# knixx_HAT_00.net
KiCad netlist of a schematic drawn in Altium Designer
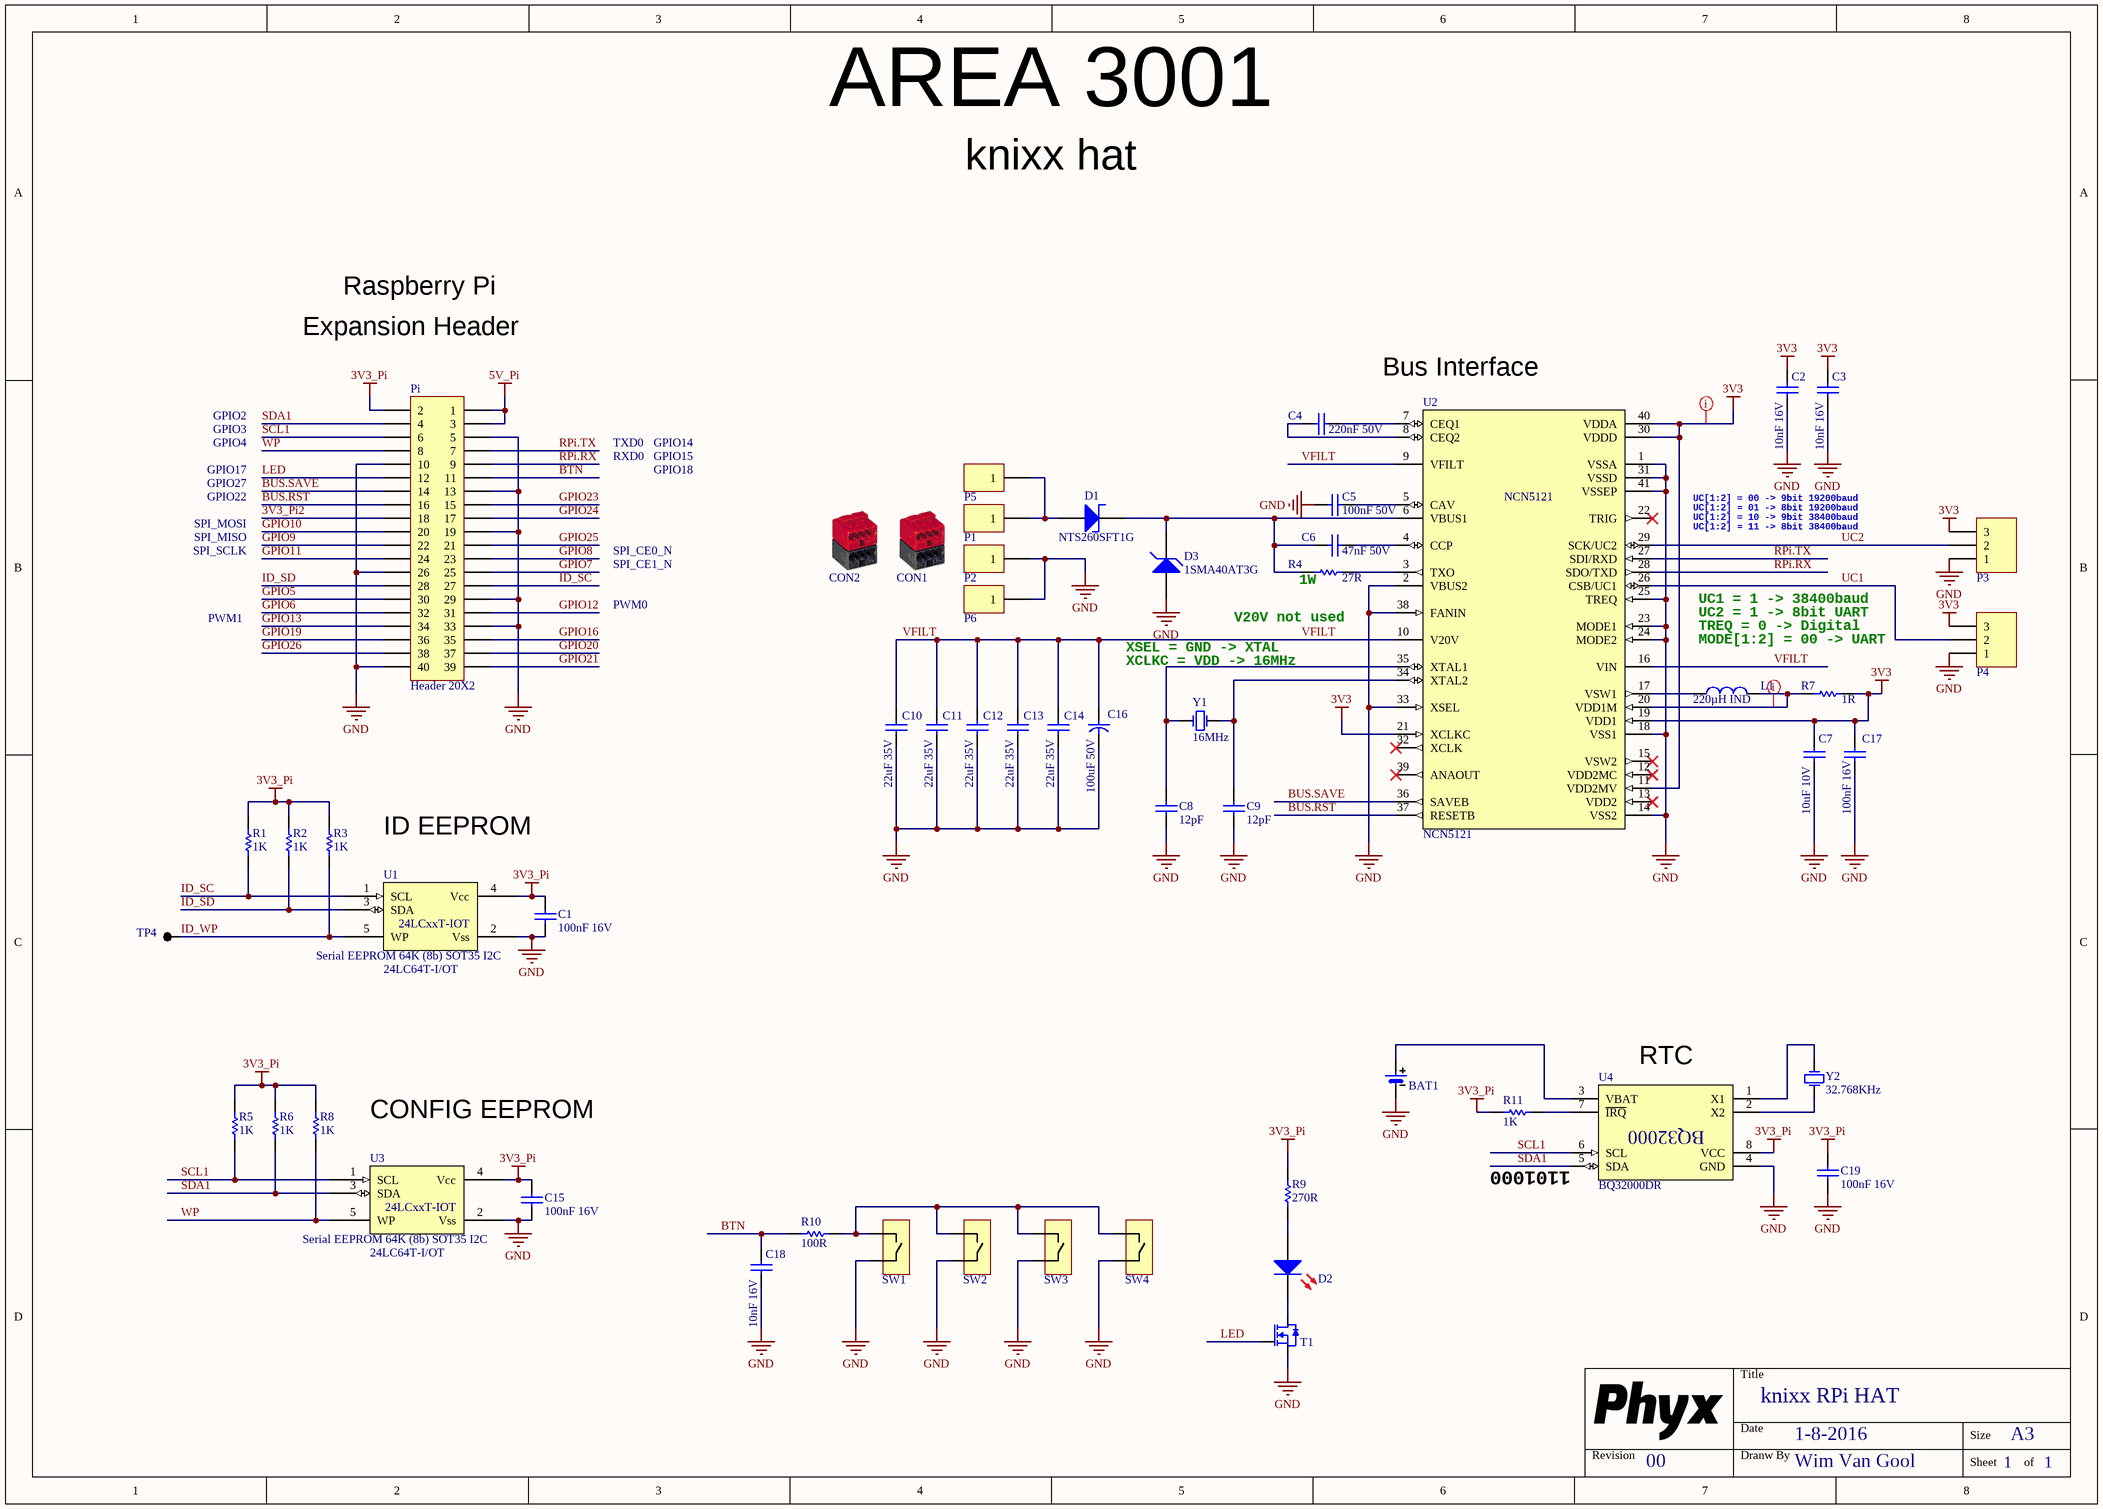
[diagram p0: knixx_HAT_00.SchDoc]

(export (version "E")
  (design (tool "Eeschema 10.0.6"))
  (components
    (comp (ref "BAT1")
      (value "BR-1220/HFN 35mAh")
      (footprint "BR-1220_HFN")
      (description "=Description")
      (libsource (lib "Phyx_Components") (part "BAT_2"))
    )
    (comp (ref "C1")
      (value "100nF 16V")
      (footprint "C0603_N")
      (description "Capacitor Ceramic")
      (fields (field (name "Comment") "CAP_CERAMIC"))
      (libsource (lib "Phyx_Components") (part "CAP_CERAMIC"))
    )
    (comp (ref "C2")
      (value "10nF 16V")
      (footprint "C0603_N")
      (description "Capacitor Ceramic")
      (fields (field (name "Comment") "CAP_CERAMIC"))
      (libsource (lib "Phyx_Components") (part "CAP_CERAMIC"))
    )
    (comp (ref "C3")
      (value "10nF 16V")
      (footprint "C0603_N")
      (description "Capacitor Ceramic")
      (fields (field (name "Comment") "CAP_CERAMIC"))
      (libsource (lib "Phyx_Components") (part "CAP_CERAMIC"))
    )
    (comp (ref "C4")
      (value "220nF 50V")
      (footprint "C0805_N")
      (description "Capacitor Ceramic")
      (fields (field (name "Comment") "CAP_CERAMIC"))
      (libsource (lib "Phyx_Components") (part "CAP_CERAMIC"))
    )
    (comp (ref "C5")
      (value "100nF 50V")
      (footprint "C0603_N")
      (description "Capacitor Ceramic")
      (fields (field (name "Comment") "CAP_CERAMIC"))
      (libsource (lib "Phyx_Components") (part "CAP_CERAMIC"))
    )
    (comp (ref "C6")
      (value "47nF 50V")
      (footprint "C0603_N")
      (description "Capacitor Ceramic")
      (fields (field (name "Comment") "CAP_CERAMIC"))
      (libsource (lib "Phyx_Components") (part "CAP_CERAMIC"))
    )
    (comp (ref "C7")
      (value "10uF 10V")
      (footprint "C0805_N")
      (description "Capacitor Ceramic")
      (fields (field (name "Comment") "CAP_CERAMIC"))
      (libsource (lib "Phyx_Components") (part "CAP_CERAMIC"))
    )
    (comp (ref "C8")
      (value "12pF")
      (footprint "C0603_N")
      (description "Capacitor Ceramic")
      (fields (field (name "Comment") "CAP_CERAMIC"))
      (libsource (lib "Phyx_Components") (part "CAP_CERAMIC"))
    )
    (comp (ref "C9")
      (value "12pF")
      (footprint "C0603_N")
      (description "Capacitor Ceramic")
      (fields (field (name "Comment") "CAP_CERAMIC"))
      (libsource (lib "Phyx_Components") (part "CAP_CERAMIC"))
    )
    (comp (ref "C10")
      (value "22uF 35V")
      (footprint "C1206_N")
      (description "Capacitor Ceramic")
      (fields (field (name "Comment") "CAP_CERAMIC"))
      (libsource (lib "Phyx_Components") (part "CAP_CERAMIC"))
    )
    (comp (ref "C11")
      (value "22uF 35V")
      (footprint "C1206_N")
      (description "Capacitor Ceramic")
      (fields (field (name "Comment") "CAP_CERAMIC"))
      (libsource (lib "Phyx_Components") (part "CAP_CERAMIC"))
    )
    (comp (ref "C12")
      (value "22uF 35V")
      (footprint "C1206_N")
      (description "Capacitor Ceramic")
      (fields (field (name "Comment") "CAP_CERAMIC"))
      (libsource (lib "Phyx_Components") (part "CAP_CERAMIC"))
    )
    (comp (ref "C13")
      (value "22uF 35V")
      (footprint "C1206_N")
      (description "Capacitor Ceramic")
      (fields (field (name "Comment") "CAP_CERAMIC"))
      (libsource (lib "Phyx_Components") (part "CAP_CERAMIC"))
    )
    (comp (ref "C14")
      (value "22uF 35V")
      (footprint "C1206_N")
      (description "Capacitor Ceramic")
      (fields (field (name "Comment") "CAP_CERAMIC"))
      (libsource (lib "Phyx_Components") (part "CAP_CERAMIC"))
    )
    (comp (ref "C15")
      (value "100nF 16V")
      (footprint "C0603_N")
      (description "Capacitor Ceramic")
      (fields (field (name "Comment") "CAP_CERAMIC"))
      (libsource (lib "Phyx_Components") (part "CAP_CERAMIC"))
    )
    (comp (ref "C16")
      (value "100uF 50V")
      (footprint "C_8x11.5_3.5mm")
      (description "Capacitor electrolyt")
      (fields (field (name "Comment") "CAP_POL"))
      (libsource (lib "Phyx_Components") (part "CAP_POL"))
    )
    (comp (ref "C17")
      (value "100nF 16V")
      (footprint "C0603_N")
      (description "Capacitor Ceramic")
      (fields (field (name "Comment") "CAP_CERAMIC"))
      (libsource (lib "Phyx_Components") (part "CAP_CERAMIC"))
    )
    (comp (ref "C18")
      (value "10nF 16V")
      (footprint "C0603_N")
      (description "Capacitor Ceramic")
      (fields (field (name "Comment") "CAP_CERAMIC"))
      (libsource (lib "Phyx_Components") (part "CAP_CERAMIC"))
    )
    (comp (ref "C19")
      (value "100nF 16V")
      (footprint "C0603_N")
      (description "Capacitor Ceramic")
      (fields (field (name "Comment") "CAP_CERAMIC"))
      (libsource (lib "Phyx_Components") (part "CAP_CERAMIC"))
    )
    (comp (ref "CON1")
      (value "CONNECTOR FOR EIB APPLICATIONS PUSH-WIRE® CONNECTION")
      (footprint "WAGO_243-211")
      (libsource (lib "Phyx_Components") (part "WAGO_243-211"))
    )
    (comp (ref "CON2")
      (value "CONNECTOR FOR EIB APPLICATIONS PUSH-WIRE® CONNECTION")
      (footprint "WAGO_243-211")
      (libsource (lib "Phyx_Components") (part "WAGO_243-211"))
    )
    (comp (ref "D1")
      (value "NTS260SFT1G")
      (footprint "ON_SOD-123FL")
      (description "=Description")
      (fields (field (name "Comment") "NTS260SFT1G  Schottky Rectifier, Single, 60 V, 2 A, SOD-123, 650 mV"))
      (libsource (lib "Phyx_Components") (part "Schottky_21"))
    )
    (comp (ref "D2")
      (value "Default 0805 Red LED")
      (footprint "LED_0805_RD")
      (description "=Description")
      (libsource (lib "Phyx_Components") (part "LED_RED"))
    )
    (comp (ref "D3")
      (value "1SMA40AT3G")
      (footprint "SMA_AC")
      (description "=Description")
      (fields (field (name "Comment") "TVS Diode 40V 400W Unidirectional DO-214AC"))
      (libsource (lib "Phyx_Components") (part "TVS_AC"))
    )
    (comp (ref "L1")
      (value "220µH IND")
      (footprint "IND_6045")
      (fields (field (name "Comment") "220µH INDUCTOR"))
      (libsource (lib "Phyx_Components") (part "INDUCTOR"))
    )
    (comp (ref "P1")
      (value "SOLDER PIN FOR PCBS UP TO 2 MM")
      (footprint "WAGO_243-131")
      (libsource (lib "Phyx_Components") (part "Header 1"))
    )
    (comp (ref "P2")
      (value "SOLDER PIN FOR PCBS UP TO 2 MM")
      (footprint "WAGO_243-131")
      (libsource (lib "Phyx_Components") (part "Header 1"))
    )
    (comp (ref "P3")
      (value "Header 3")
      (footprint "HDR1X3")
      (libsource (lib "Phyx_Components") (part "Header 3"))
    )
    (comp (ref "P4")
      (value "Header 3")
      (footprint "HDR1X3")
      (libsource (lib "Phyx_Components") (part "Header 3"))
    )
    (comp (ref "P5")
      (value "SOLDER PIN FOR PCBS UP TO 2 MM")
      (footprint "WAGO_243-131")
      (libsource (lib "Phyx_Components") (part "Header 1"))
    )
    (comp (ref "P6")
      (value "SOLDER PIN FOR PCBS UP TO 2 MM")
      (footprint "WAGO_243-131")
      (libsource (lib "Phyx_Components") (part "Header 1"))
    )
    (comp (ref "Pi")
      (value "Header 20X2")
      (footprint "RCPT2X20")
      (description "=Description")
      (libsource (lib "Phyx_Components") (part "Header 20X2"))
    )
    (comp (ref "R1")
      (value "1K")
      (footprint "R0603_N")
      (fields (field (name "Comment") "RESISTOR"))
      (libsource (lib "Phyx_Components") (part "RESISTOR"))
    )
    (comp (ref "R2")
      (value "1K")
      (footprint "R0603_N")
      (fields (field (name "Comment") "RESISTOR"))
      (libsource (lib "Phyx_Components") (part "RESISTOR"))
    )
    (comp (ref "R3")
      (value "1K")
      (footprint "R0603_N")
      (fields (field (name "Comment") "RESISTOR"))
      (libsource (lib "Phyx_Components") (part "RESISTOR"))
    )
    (comp (ref "R4")
      (value "27R")
      (footprint "R2512")
      (fields (field (name "Comment") "RESISTOR"))
      (libsource (lib "Phyx_Components") (part "RESISTOR"))
    )
    (comp (ref "R5")
      (value "1K")
      (footprint "R0603_N")
      (fields (field (name "Comment") "RESISTOR"))
      (libsource (lib "Phyx_Components") (part "RESISTOR"))
    )
    (comp (ref "R6")
      (value "1K")
      (footprint "R0603_N")
      (fields (field (name "Comment") "RESISTOR"))
      (libsource (lib "Phyx_Components") (part "RESISTOR"))
    )
    (comp (ref "R7")
      (value "1R")
      (footprint "R0603_N")
      (fields (field (name "Comment") "RESISTOR"))
      (libsource (lib "Phyx_Components") (part "RESISTOR"))
    )
    (comp (ref "R8")
      (value "1K")
      (footprint "R0603_N")
      (fields (field (name "Comment") "RESISTOR"))
      (libsource (lib "Phyx_Components") (part "RESISTOR"))
    )
    (comp (ref "R9")
      (value "270R")
      (footprint "R0603_N")
      (fields (field (name "Comment") "RESISTOR"))
      (libsource (lib "Phyx_Components") (part "RESISTOR"))
    )
    (comp (ref "R10")
      (value "100R")
      (footprint "R0603_N")
      (fields (field (name "Comment") "RESISTOR"))
      (libsource (lib "Phyx_Components") (part "RESISTOR"))
    )
    (comp (ref "R11")
      (value "1K")
      (footprint "R0603_N")
      (fields (field (name "Comment") "RESISTOR"))
      (libsource (lib "Phyx_Components") (part "RESISTOR"))
    )
    (comp (ref "SW1")
      (value "LP RA SMD tact sw W/BOSS")
      (footprint "EVQP7M01K")
      (libsource (lib "Phyx_Components") (part "SW_TACT"))
    )
    (comp (ref "SW2")
      (value "Default TH TACT")
      (footprint "TACTSW")
      (libsource (lib "Phyx_Components") (part "SW_TACT"))
    )
    (comp (ref "SW3")
      (value "LP RA SMD tact sw W/BOSS")
      (footprint "EVQP7M01K")
      (libsource (lib "Phyx_Components") (part "SW_TACT"))
    )
    (comp (ref "SW4")
      (value "Default TH TACT")
      (footprint "TACTSW")
      (libsource (lib "Phyx_Components") (part "SW_TACT"))
    )
    (comp (ref "T1")
      (value "0.2A N-Ch MOSFET Vgs 3.2")
      (footprint "SOT23-3")
      (libsource (lib "Phyx_Components") (part "N_MOSFET_GSD"))
    )
    (comp (ref "TP4")
      (value "TEST_PAD")
      (footprint "TP_1.2mm_0.6mm")
      (libsource (lib "Phyx_Components") (part "TEST_PAD"))
    )
    (comp (ref "U1")
      (value "Serial EEPROM 64K (8b) SOT35 I2C")
      (footprint "SOT23-5")
      (description "=Description")
      (fields (field (name "ALTIUM_VALUE") "24LC64T-I/OT"))
      (libsource (lib "Phyx_Components") (part "24LCxxT-IOT"))
    )
    (comp (ref "U2")
      (value "NCN5121")
      (footprint "ONS_QFN40_6x6")
      (description "=Description")
      (fields (field (name "Comment") "KNX Transceiver for Twisted Pair Networks"))
      (libsource (lib "Phyx_Components") (part "NCN5121"))
    )
    (comp (ref "U3")
      (value "Serial EEPROM 64K (8b) SOT35 I2C")
      (footprint "SOT23-5")
      (description "=Description")
      (fields (field (name "ALTIUM_VALUE") "24LC64T-I/OT"))
      (libsource (lib "Phyx_Components") (part "24LCxxT-IOT"))
    )
    (comp (ref "U4")
      (value "BQ32000DR")
      (footprint "SOIC_N_8")
      (description "=Description")
      (fields (field (name "Comment") "I2C RTC Ti BQ32000"))
      (libsource (lib "Phyx_Components") (part "BQ32000"))
    )
    (comp (ref "Y1")
      (value "16MHz")
      (footprint "HC49US_SMD")
      (description "Crystal Oscillator")
      (fields (field (name "Comment") "16MHz 20pF HC49S Fox"))
      (libsource (lib "Phyx_Components") (part "XTAL"))
    )
    (comp (ref "Y2")
      (value "32.768KHz")
      (footprint "CMR200T")
      (description "Crystal Oscillator")
      (fields (field (name "Comment") "32.768Khz CMR200 12.5pF"))
      (libsource (lib "Phyx_Components") (part "XTAL"))
    )
  )
  (nets
    (net (code "1") (name "/3V3_Pi2") (class "Default")
      (node (ref "Pi") (pin "18") (pinfunction "18_18") (pintype "passive"))
    )
    (net (code "2") (name "/BTN") (class "Default")
      (node (ref "C18") (pin "1") (pinfunction "1_1") (pintype "passive"))
      (node (ref "Pi") (pin "11") (pinfunction "11_11") (pintype "passive"))
      (node (ref "R10") (pin "2") (pinfunction "2_2") (pintype "passive"))
    )
    (net (code "3") (name "/BUS.RST") (class "Default")
      (node (ref "Pi") (pin "16") (pinfunction "16_16") (pintype "passive"))
      (node (ref "U2") (pin "37") (pinfunction "RESETB_37") (pintype "output"))
    )
    (net (code "4") (name "/BUS.SAVE") (class "Default")
      (node (ref "Pi") (pin "14") (pinfunction "14_14") (pintype "passive"))
      (node (ref "U2") (pin "36") (pinfunction "SAVEB_36") (pintype "output"))
    )
    (net (code "5") (name "/GPIO5") (class "Default")
      (node (ref "Pi") (pin "30") (pinfunction "30_30") (pintype "passive"))
    )
    (net (code "6") (name "/GPIO6") (class "Default")
      (node (ref "Pi") (pin "32") (pinfunction "32_32") (pintype "passive"))
    )
    (net (code "7") (name "/GPIO7") (class "Default")
      (node (ref "Pi") (pin "25") (pinfunction "25_25") (pintype "passive"))
    )
    (net (code "8") (name "/GPIO8") (class "Default")
      (node (ref "Pi") (pin "23") (pinfunction "23_23") (pintype "passive"))
    )
    (net (code "9") (name "/GPIO9") (class "Default")
      (node (ref "Pi") (pin "22") (pinfunction "22_22") (pintype "passive"))
    )
    (net (code "10") (name "/GPIO10") (class "Default")
      (node (ref "Pi") (pin "20") (pinfunction "20_20") (pintype "passive"))
    )
    (net (code "11") (name "/GPIO11") (class "Default")
      (node (ref "Pi") (pin "24") (pinfunction "24_24") (pintype "passive"))
    )
    (net (code "12") (name "/GPIO12") (class "Default")
      (node (ref "Pi") (pin "31") (pinfunction "31_31") (pintype "passive"))
    )
    (net (code "13") (name "/GPIO13") (class "Default")
      (node (ref "Pi") (pin "34") (pinfunction "34_34") (pintype "passive"))
    )
    (net (code "14") (name "/GPIO16") (class "Default")
      (node (ref "Pi") (pin "35") (pinfunction "35_35") (pintype "passive"))
    )
    (net (code "15") (name "/GPIO19") (class "Default")
      (node (ref "Pi") (pin "36") (pinfunction "36_36") (pintype "passive"))
    )
    (net (code "16") (name "/GPIO20") (class "Default")
      (node (ref "Pi") (pin "37") (pinfunction "37_37") (pintype "passive"))
    )
    (net (code "17") (name "/GPIO21") (class "Default")
      (node (ref "Pi") (pin "39") (pinfunction "39_39") (pintype "passive"))
    )
    (net (code "18") (name "/GPIO23") (class "Default")
      (node (ref "Pi") (pin "15") (pinfunction "15_15") (pintype "passive"))
    )
    (net (code "19") (name "/GPIO24") (class "Default")
      (node (ref "Pi") (pin "17") (pinfunction "17_17") (pintype "passive"))
    )
    (net (code "20") (name "/GPIO25") (class "Default")
      (node (ref "Pi") (pin "21") (pinfunction "21_21") (pintype "passive"))
    )
    (net (code "21") (name "/GPIO26") (class "Default")
      (node (ref "Pi") (pin "38") (pinfunction "38_38") (pintype "passive"))
    )
    (net (code "22") (name "/ID_SC") (class "Default")
      (node (ref "Pi") (pin "27") (pinfunction "27_27") (pintype "passive"))
      (node (ref "R1") (pin "2") (pinfunction "2_2") (pintype "passive"))
      (node (ref "U1") (pin "1") (pinfunction "SCL_1") (pintype "input"))
    )
    (net (code "23") (name "/ID_SD") (class "Default")
      (node (ref "Pi") (pin "28") (pinfunction "28_28") (pintype "passive"))
      (node (ref "R2") (pin "2") (pinfunction "2_2") (pintype "passive"))
      (node (ref "U1") (pin "3") (pinfunction "SDA_3") (pintype "bidirectional"))
    )
    (net (code "24") (name "/ID_WP") (class "Default")
      (node (ref "R3") (pin "2") (pinfunction "2_2") (pintype "passive"))
      (node (ref "TP4") (pin "1") (pinfunction "1_1") (pintype "passive"))
      (node (ref "U1") (pin "5") (pinfunction "WP_5") (pintype "passive"))
    )
    (net (code "25") (name "/LED") (class "Default")
      (node (ref "Pi") (pin "12") (pinfunction "12_12") (pintype "passive"))
      (node (ref "T1") (pin "1") (pinfunction "G_1") (pintype "passive"))
    )
    (net (code "26") (name "/RPi.RX") (class "Default")
      (node (ref "Pi") (pin "9") (pinfunction "9_9") (pintype "passive"))
      (node (ref "U2") (pin "28") (pinfunction "SDO/TXD_28") (pintype "output"))
    )
    (net (code "27") (name "/RPi.TX") (class "Default")
      (node (ref "Pi") (pin "7") (pinfunction "7_7") (pintype "passive"))
      (node (ref "U2") (pin "27") (pinfunction "SDI/RXD_27") (pintype "input"))
    )
    (net (code "28") (name "/SCL1") (class "Default")
      (node (ref "Pi") (pin "6") (pinfunction "6_6") (pintype "passive"))
      (node (ref "R5") (pin "2") (pinfunction "2_2") (pintype "passive"))
      (node (ref "U3") (pin "1") (pinfunction "SCL_1") (pintype "input"))
      (node (ref "U4") (pin "6") (pinfunction "SCL_6") (pintype "input"))
    )
    (net (code "29") (name "/SDA1") (class "Default")
      (node (ref "Pi") (pin "4") (pinfunction "4_4") (pintype "passive"))
      (node (ref "R6") (pin "2") (pinfunction "2_2") (pintype "passive"))
      (node (ref "U3") (pin "3") (pinfunction "SDA_3") (pintype "bidirectional"))
      (node (ref "U4") (pin "5") (pinfunction "SDA_5") (pintype "bidirectional"))
    )
    (net (code "30") (name "/UC1") (class "Default")
      (node (ref "P4") (pin "2") (pinfunction "2_2") (pintype "passive"))
      (node (ref "U2") (pin "26") (pinfunction "CSB/UC1_26") (pintype "bidirectional"))
    )
    (net (code "31") (name "/UC2") (class "Default")
      (node (ref "P3") (pin "2") (pinfunction "2_2") (pintype "passive"))
      (node (ref "U2") (pin "29") (pinfunction "SCK/UC2_29") (pintype "bidirectional"))
    )
    (net (code "32") (name "/VFILT") (class "Default")
      (node (ref "C10") (pin "1") (pinfunction "1_1") (pintype "passive"))
      (node (ref "C11") (pin "1") (pinfunction "1_1") (pintype "passive"))
      (node (ref "C12") (pin "1") (pinfunction "1_1") (pintype "passive"))
      (node (ref "C13") (pin "1") (pinfunction "1_1") (pintype "passive"))
      (node (ref "C14") (pin "1") (pinfunction "1_1") (pintype "passive"))
      (node (ref "C16") (pin "1") (pinfunction "1_1") (pintype "passive"))
      (node (ref "U2") (pin "10") (pinfunction "V20V_10") (pintype "power_in"))
      (node (ref "U2") (pin "16") (pinfunction "VIN_16") (pintype "power_in"))
      (node (ref "U2") (pin "9") (pinfunction "VFILT_9") (pintype "power_in"))
    )
    (net (code "33") (name "/WP") (class "Default")
      (node (ref "Pi") (pin "8") (pinfunction "8_8") (pintype "passive"))
      (node (ref "R8") (pin "2") (pinfunction "2_2") (pintype "passive"))
      (node (ref "U3") (pin "5") (pinfunction "WP_5") (pintype "passive"))
    )
    (net (code "34") (name "3V3") (class "Default")
      (node (ref "C17") (pin "1") (pinfunction "1_1") (pintype "passive"))
      (node (ref "C2") (pin "1") (pinfunction "1_1") (pintype "passive"))
      (node (ref "C3") (pin "1") (pinfunction "1_1") (pintype "passive"))
      (node (ref "C7") (pin "1") (pinfunction "1_1") (pintype "passive"))
      (node (ref "P3") (pin "3") (pinfunction "3_3") (pintype "passive"))
      (node (ref "P4") (pin "3") (pinfunction "3_3") (pintype "passive"))
      (node (ref "R7") (pin "1") (pinfunction "1_1") (pintype "passive"))
      (node (ref "U2") (pin "11") (pinfunction "VDD2MV_11") (pintype "input"))
      (node (ref "U2") (pin "19") (pinfunction "VDD1_19") (pintype "input"))
      (node (ref "U2") (pin "21") (pinfunction "XCLKC_21") (pintype "input"))
      (node (ref "U2") (pin "30") (pinfunction "VDDD_30") (pintype "power_in"))
      (node (ref "U2") (pin "40") (pinfunction "VDDA_40") (pintype "power_in"))
    )
    (net (code "35") (name "3V3_Pi") (class "Default")
      (node (ref "C1") (pin "1") (pinfunction "1_1") (pintype "passive"))
      (node (ref "C15") (pin "1") (pinfunction "1_1") (pintype "passive"))
      (node (ref "C19") (pin "1") (pinfunction "1_1") (pintype "passive"))
      (node (ref "Pi") (pin "2") (pinfunction "2_2") (pintype "passive"))
      (node (ref "R1") (pin "1") (pinfunction "1_1") (pintype "passive"))
      (node (ref "R11") (pin "1") (pinfunction "1_1") (pintype "passive"))
      (node (ref "R2") (pin "1") (pinfunction "1_1") (pintype "passive"))
      (node (ref "R3") (pin "1") (pinfunction "1_1") (pintype "passive"))
      (node (ref "R5") (pin "1") (pinfunction "1_1") (pintype "passive"))
      (node (ref "R6") (pin "1") (pinfunction "1_1") (pintype "passive"))
      (node (ref "R8") (pin "1") (pinfunction "1_1") (pintype "passive"))
      (node (ref "R9") (pin "1") (pinfunction "1_1") (pintype "passive"))
      (node (ref "U1") (pin "4") (pinfunction "Vcc_4") (pintype "passive"))
      (node (ref "U3") (pin "4") (pinfunction "Vcc_4") (pintype "passive"))
      (node (ref "U4") (pin "8") (pinfunction "VCC_8") (pintype "power_in"))
    )
    (net (code "36") (name "5V_Pi") (class "Default")
      (node (ref "Pi") (pin "1") (pinfunction "1_1") (pintype "passive"))
      (node (ref "Pi") (pin "3") (pinfunction "3_3") (pintype "passive"))
    )
    (net (code "37") (name "GND") (class "Default")
      (node (ref "BAT1") (pin "2") (pinfunction "2_2") (pintype "passive"))
      (node (ref "C1") (pin "2") (pinfunction "2_2") (pintype "passive"))
      (node (ref "C10") (pin "2") (pinfunction "2_2") (pintype "passive"))
      (node (ref "C11") (pin "2") (pinfunction "2_2") (pintype "passive"))
      (node (ref "C12") (pin "2") (pinfunction "2_2") (pintype "passive"))
      (node (ref "C13") (pin "2") (pinfunction "2_2") (pintype "passive"))
      (node (ref "C14") (pin "2") (pinfunction "2_2") (pintype "passive"))
      (node (ref "C15") (pin "2") (pinfunction "2_2") (pintype "passive"))
      (node (ref "C16") (pin "2") (pinfunction "2_2") (pintype "passive"))
      (node (ref "C17") (pin "2") (pinfunction "2_2") (pintype "passive"))
      (node (ref "C18") (pin "2") (pinfunction "2_2") (pintype "passive"))
      (node (ref "C19") (pin "2") (pinfunction "2_2") (pintype "passive"))
      (node (ref "C2") (pin "2") (pinfunction "2_2") (pintype "passive"))
      (node (ref "C3") (pin "2") (pinfunction "2_2") (pintype "passive"))
      (node (ref "C5") (pin "2") (pinfunction "2_2") (pintype "passive"))
      (node (ref "C7") (pin "2") (pinfunction "2_2") (pintype "passive"))
      (node (ref "C8") (pin "2") (pinfunction "2_2") (pintype "passive"))
      (node (ref "C9") (pin "2") (pinfunction "2_2") (pintype "passive"))
      (node (ref "D3") (pin "A") (pinfunction "A_A") (pintype "passive"))
      (node (ref "P2") (pin "1") (pinfunction "1_1") (pintype "passive"))
      (node (ref "P3") (pin "1") (pinfunction "1_1") (pintype "passive"))
      (node (ref "P4") (pin "1") (pinfunction "1_1") (pintype "passive"))
      (node (ref "P6") (pin "1") (pinfunction "1_1") (pintype "passive"))
      (node (ref "Pi") (pin "10") (pinfunction "10_10") (pintype "passive"))
      (node (ref "Pi") (pin "13") (pinfunction "13_13") (pintype "passive"))
      (node (ref "Pi") (pin "19") (pinfunction "19_19") (pintype "passive"))
      (node (ref "Pi") (pin "26") (pinfunction "26_26") (pintype "passive"))
      (node (ref "Pi") (pin "29") (pinfunction "29_29") (pintype "passive"))
      (node (ref "Pi") (pin "33") (pinfunction "33_33") (pintype "passive"))
      (node (ref "Pi") (pin "40") (pinfunction "40_40") (pintype "passive"))
      (node (ref "Pi") (pin "5") (pinfunction "5_5") (pintype "passive"))
      (node (ref "SW1") (pin "2") (pinfunction "2_2") (pintype "passive"))
      (node (ref "SW2") (pin "2") (pinfunction "2_2") (pintype "passive"))
      (node (ref "SW3") (pin "2") (pinfunction "2_2") (pintype "passive"))
      (node (ref "SW4") (pin "2") (pinfunction "2_2") (pintype "passive"))
      (node (ref "T1") (pin "2") (pinfunction "S_2") (pintype "passive"))
      (node (ref "U1") (pin "2") (pinfunction "Vss_2") (pintype "passive"))
      (node (ref "U2") (pin "1") (pinfunction "VSSA_1") (pintype "power_in"))
      (node (ref "U2") (pin "14") (pinfunction "VSS2_14") (pintype "power_in"))
      (node (ref "U2") (pin "18") (pinfunction "VSS1_18") (pintype "power_in"))
      (node (ref "U2") (pin "2") (pinfunction "VBUS2_2") (pintype "power_in"))
      (node (ref "U2") (pin "23") (pinfunction "MODE1_23") (pintype "input"))
      (node (ref "U2") (pin "24") (pinfunction "MODE2_24") (pintype "input"))
      (node (ref "U2") (pin "25") (pinfunction "TREQ_25") (pintype "input"))
      (node (ref "U2") (pin "31") (pinfunction "VSSD_31") (pintype "power_in"))
      (node (ref "U2") (pin "33") (pinfunction "XSEL_33") (pintype "input"))
      (node (ref "U2") (pin "38") (pinfunction "FANIN_38") (pintype "input"))
      (node (ref "U2") (pin "41") (pinfunction "VSSEP_41") (pintype "power_in"))
      (node (ref "U3") (pin "2") (pinfunction "Vss_2") (pintype "passive"))
      (node (ref "U4") (pin "4") (pinfunction "GND_4") (pintype "power_in"))
    )
    (net (code "38") (name "Net-(D1-A)") (class "Default")
      (node (ref "D1") (pin "2") (pinfunction "A_2") (pintype "passive"))
      (node (ref "P1") (pin "1") (pinfunction "1_1") (pintype "passive"))
      (node (ref "P5") (pin "1") (pinfunction "1_1") (pintype "passive"))
    )
    (net (code "39") (name "Net-(D1-C)") (class "Default")
      (node (ref "C6") (pin "2") (pinfunction "2_2") (pintype "passive"))
      (node (ref "D1") (pin "1") (pinfunction "C_1") (pintype "passive"))
      (node (ref "D3") (pin "C") (pinfunction "C_C") (pintype "passive"))
      (node (ref "R4") (pin "2") (pinfunction "2_2") (pintype "passive"))
      (node (ref "U2") (pin "6") (pinfunction "VBUS1_6") (pintype "power_in"))
    )
    (net (code "40") (name "Net-(D2-A)") (class "Default")
      (node (ref "D2") (pin "1") (pinfunction "A_1") (pintype "passive"))
      (node (ref "R9") (pin "2") (pinfunction "2_2") (pintype "passive"))
    )
    (net (code "41") (name "Net-(D2-K)") (class "Default")
      (node (ref "D2") (pin "2") (pinfunction "K_2") (pintype "passive"))
      (node (ref "T1") (pin "3") (pinfunction "D_3") (pintype "passive"))
    )
    (net (code "42") (name "Net-(R10-Pad1)") (class "Default")
      (node (ref "R10") (pin "1") (pinfunction "1_1") (pintype "passive"))
      (node (ref "SW1") (pin "1") (pinfunction "1_1") (pintype "passive"))
      (node (ref "SW2") (pin "1") (pinfunction "1_1") (pintype "passive"))
      (node (ref "SW3") (pin "1") (pinfunction "1_1") (pintype "passive"))
      (node (ref "SW4") (pin "1") (pinfunction "1_1") (pintype "passive"))
    )
    (net (code "43") (name "Net-(U2-CAV)") (class "Default")
      (node (ref "C5") (pin "1") (pinfunction "1_1") (pintype "passive"))
      (node (ref "U2") (pin "5") (pinfunction "CAV_5") (pintype "bidirectional"))
    )
    (net (code "44") (name "Net-(U2-CCP)") (class "Default")
      (node (ref "C6") (pin "1") (pinfunction "1_1") (pintype "passive"))
      (node (ref "U2") (pin "4") (pinfunction "CCP_4") (pintype "bidirectional"))
    )
    (net (code "45") (name "Net-(U2-CEQ1)") (class "Default")
      (node (ref "C4") (pin "1") (pinfunction "1_1") (pintype "passive"))
      (node (ref "U2") (pin "7") (pinfunction "CEQ1_7") (pintype "bidirectional"))
    )
    (net (code "46") (name "Net-(U2-CEQ2)") (class "Default")
      (node (ref "C4") (pin "2") (pinfunction "2_2") (pintype "passive"))
      (node (ref "U2") (pin "8") (pinfunction "CEQ2_8") (pintype "bidirectional"))
    )
    (net (code "47") (name "Net-(U2-TXO)") (class "Default")
      (node (ref "R4") (pin "1") (pinfunction "1_1") (pintype "passive"))
      (node (ref "U2") (pin "3") (pinfunction "TXO_3") (pintype "output"))
    )
    (net (code "48") (name "Net-(U2-VDD1M)") (class "Default")
      (node (ref "L1") (pin "2") (pinfunction "2_2") (pintype "passive"))
      (node (ref "R7") (pin "2") (pinfunction "2_2") (pintype "passive"))
      (node (ref "U2") (pin "20") (pinfunction "VDD1M_20") (pintype "input"))
    )
    (net (code "49") (name "Net-(U2-VSW1)") (class "Default")
      (node (ref "L1") (pin "1") (pinfunction "1_1") (pintype "passive"))
      (node (ref "U2") (pin "17") (pinfunction "VSW1_17") (pintype "output"))
    )
    (net (code "50") (name "Net-(U2-XTAL1)") (class "Default")
      (node (ref "C8") (pin "1") (pinfunction "1_1") (pintype "passive"))
      (node (ref "U2") (pin "35") (pinfunction "XTAL1_35") (pintype "bidirectional"))
      (node (ref "Y1") (pin "1") (pinfunction "OSC1_1") (pintype "passive"))
    )
    (net (code "51") (name "Net-(U2-XTAL2)") (class "Default")
      (node (ref "C9") (pin "1") (pinfunction "1_1") (pintype "passive"))
      (node (ref "U2") (pin "34") (pinfunction "XTAL2_34") (pintype "bidirectional"))
      (node (ref "Y1") (pin "2") (pinfunction "OSC2_2") (pintype "passive"))
    )
    (net (code "52") (name "Net-(U4-VBAT)") (class "Default")
      (node (ref "BAT1") (pin "1") (pinfunction "1_1") (pintype "passive"))
      (node (ref "U4") (pin "3") (pinfunction "VBAT_3") (pintype "power_in"))
    )
    (net (code "53") (name "Net-(U4-X1)") (class "Default")
      (node (ref "U4") (pin "1") (pinfunction "X1_1") (pintype "passive"))
      (node (ref "Y2") (pin "2") (pinfunction "OSC2_2") (pintype "passive"))
    )
    (net (code "54") (name "Net-(U4-X2)") (class "Default")
      (node (ref "U4") (pin "2") (pinfunction "X2_2") (pintype "passive"))
      (node (ref "Y2") (pin "1") (pinfunction "OSC1_1") (pintype "passive"))
    )
    (net (code "55") (name "Net-(U4-~{IRQ})") (class "Default")
      (node (ref "R11") (pin "2") (pinfunction "2_2") (pintype "passive"))
      (node (ref "U4") (pin "7") (pinfunction "~{IRQ}_7") (pintype "passive"))
    )
    (net (code "56") (name "unconnected-(U2-ANAOUT-Pad39)") (class "Default")
      (node (ref "U2") (pin "39") (pinfunction "ANAOUT_39") (pintype "output+no_connect"))
    )
    (net (code "57") (name "unconnected-(U2-TRIG-Pad22)") (class "Default")
      (node (ref "U2") (pin "22") (pinfunction "TRIG_22") (pintype "output+no_connect"))
    )
    (net (code "58") (name "unconnected-(U2-VDD2-Pad13)") (class "Default")
      (node (ref "U2") (pin "13") (pinfunction "VDD2_13") (pintype "input+no_connect"))
    )
    (net (code "59") (name "unconnected-(U2-VDD2MC-Pad12)") (class "Default")
      (node (ref "U2") (pin "12") (pinfunction "VDD2MC_12") (pintype "input+no_connect"))
    )
    (net (code "60") (name "unconnected-(U2-VSW2-Pad15)") (class "Default")
      (node (ref "U2") (pin "15") (pinfunction "VSW2_15") (pintype "output+no_connect"))
    )
    (net (code "61") (name "unconnected-(U2-XCLK-Pad32)") (class "Default")
      (node (ref "U2") (pin "32") (pinfunction "XCLK_32") (pintype "output+no_connect"))
    )
  )
)
